# owi-slave.net
KiCad netlist of a schematic drawn in EAGLE
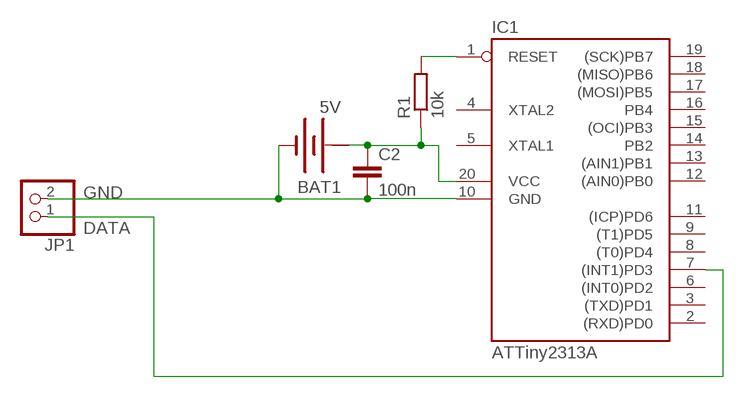
[diagram p0: schematic, sheet 1]

(export (version "E")
  (design (tool "Eeschema 10.0.6"))
  (components
    (comp (ref "BAT1")
      (value "5V")
      (footprint "eagle-import:BATTERY")
      (libsource (lib "eagle-import") (part "BATTERY"))
    )
    (comp (ref "C2")
      (value "100n")
      (footprint "eagle-import:C025-024X044")
      (libsource (lib "eagle-import") (part "C-EU025-024X044"))
    )
    (comp (ref "IC1")
      (value "ATTiny2313A")
      (footprint "eagle-import:DIL20")
      (libsource (lib "eagle-import") (part "AT90S2313P"))
    )
    (comp (ref "JP1")
      (value "PINHD-1X2")
      (footprint "eagle-import:1X02")
      (libsource (lib "eagle-import") (part "PINHD-1X2"))
    )
    (comp (ref "R1")
      (value "10k")
      (footprint "eagle-import:0207_10")
      (libsource (lib "eagle-import") (part "R-EU_0207/10"))
    )
  )
  (nets
    (net (code "1") (name "/+") (class "Default")
      (node (ref "BAT1") (pin "+@1") (pinfunction "+_+@1") (pintype "power_in"))
    )
    (net (code "2") (name "/DATA") (class "Default")
      (node (ref "IC1") (pin "7") (pinfunction "(INT1)PD3_7") (pintype "bidirectional"))
      (node (ref "JP1") (pin "1") (pinfunction "1_1") (pintype "passive"))
    )
    (net (code "3") (name "/GND") (class "Default")
      (node (ref "BAT1") (pin "-") (pinfunction "-_-") (pintype "power_in"))
      (node (ref "C2") (pin "2") (pinfunction "2_2") (pintype "passive"))
      (node (ref "IC1") (pin "10") (pinfunction "GND_10") (pintype "power_in"))
      (node (ref "JP1") (pin "2") (pinfunction "2_2") (pintype "passive"))
    )
    (net (code "4") (name "Net-(IC1-RESET)") (class "Default")
      (node (ref "IC1") (pin "1") (pinfunction "RESET_1") (pintype "bidirectional"))
      (node (ref "R1") (pin "2") (pinfunction "2_2") (pintype "passive"))
    )
    (net (code "5") (name "Net-(IC1-VCC)") (class "Default")
      (node (ref "BAT1") (pin "+") (pinfunction "+_+") (pintype "power_in"))
      (node (ref "C2") (pin "1") (pinfunction "1_1") (pintype "passive"))
      (node (ref "IC1") (pin "20") (pinfunction "VCC_20") (pintype "power_in"))
      (node (ref "R1") (pin "1") (pinfunction "1_1") (pintype "passive"))
    )
    (net (code "6") (name "unconnected-(IC1-(AIN0)PB0-Pad12)") (class "Default")
      (node (ref "IC1") (pin "12") (pinfunction "(AIN0)PB0_12") (pintype "bidirectional"))
    )
    (net (code "7") (name "unconnected-(IC1-(AIN1)PB1-Pad13)") (class "Default")
      (node (ref "IC1") (pin "13") (pinfunction "(AIN1)PB1_13") (pintype "bidirectional"))
    )
    (net (code "8") (name "unconnected-(IC1-(ICP)PD6-Pad11)") (class "Default")
      (node (ref "IC1") (pin "11") (pinfunction "(ICP)PD6_11") (pintype "bidirectional"))
    )
    (net (code "9") (name "unconnected-(IC1-(INT0)PD2-Pad6)") (class "Default")
      (node (ref "IC1") (pin "6") (pinfunction "(INT0)PD2_6") (pintype "bidirectional"))
    )
    (net (code "10") (name "unconnected-(IC1-(MISO)PB6-Pad18)") (class "Default")
      (node (ref "IC1") (pin "18") (pinfunction "(MISO)PB6_18") (pintype "bidirectional"))
    )
    (net (code "11") (name "unconnected-(IC1-(MOSI)PB5-Pad17)") (class "Default")
      (node (ref "IC1") (pin "17") (pinfunction "(MOSI)PB5_17") (pintype "bidirectional"))
    )
    (net (code "12") (name "unconnected-(IC1-(OCI)PB3-Pad15)") (class "Default")
      (node (ref "IC1") (pin "15") (pinfunction "(OCI)PB3_15") (pintype "bidirectional"))
    )
    (net (code "13") (name "unconnected-(IC1-(RXD)PD0-Pad2)") (class "Default")
      (node (ref "IC1") (pin "2") (pinfunction "(RXD)PD0_2") (pintype "bidirectional"))
    )
    (net (code "14") (name "unconnected-(IC1-(SCK)PB7-Pad19)") (class "Default")
      (node (ref "IC1") (pin "19") (pinfunction "(SCK)PB7_19") (pintype "bidirectional"))
    )
    (net (code "15") (name "unconnected-(IC1-(T0)PD4-Pad8)") (class "Default")
      (node (ref "IC1") (pin "8") (pinfunction "(T0)PD4_8") (pintype "bidirectional"))
    )
    (net (code "16") (name "unconnected-(IC1-(T1)PD5-Pad9)") (class "Default")
      (node (ref "IC1") (pin "9") (pinfunction "(T1)PD5_9") (pintype "bidirectional"))
    )
    (net (code "17") (name "unconnected-(IC1-(TXD)PD1-Pad3)") (class "Default")
      (node (ref "IC1") (pin "3") (pinfunction "(TXD)PD1_3") (pintype "bidirectional"))
    )
    (net (code "18") (name "unconnected-(IC1-PB2-Pad14)") (class "Default")
      (node (ref "IC1") (pin "14") (pinfunction "PB2_14") (pintype "bidirectional"))
    )
    (net (code "19") (name "unconnected-(IC1-PB4-Pad16)") (class "Default")
      (node (ref "IC1") (pin "16") (pinfunction "PB4_16") (pintype "bidirectional"))
    )
    (net (code "20") (name "unconnected-(IC1-XTAL1-Pad5)") (class "Default")
      (node (ref "IC1") (pin "5") (pinfunction "XTAL1_5") (pintype "bidirectional"))
    )
    (net (code "21") (name "unconnected-(IC1-XTAL2-Pad4)") (class "Default")
      (node (ref "IC1") (pin "4") (pinfunction "XTAL2_4") (pintype "bidirectional"))
    )
  )
)
